# pwm-dac-rev2.net
KiCad netlist of a schematic drawn in EAGLE
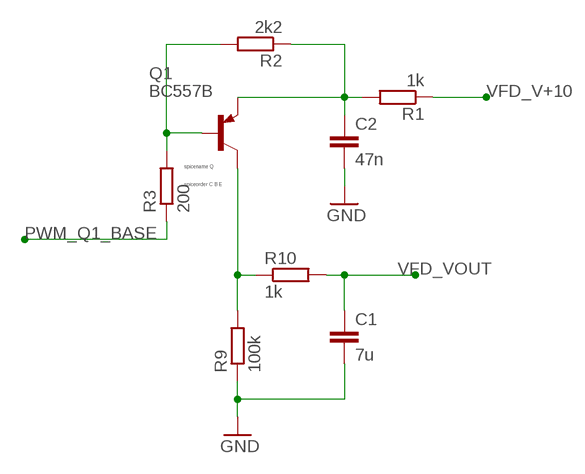
[diagram p0: schematic, sheet 1]
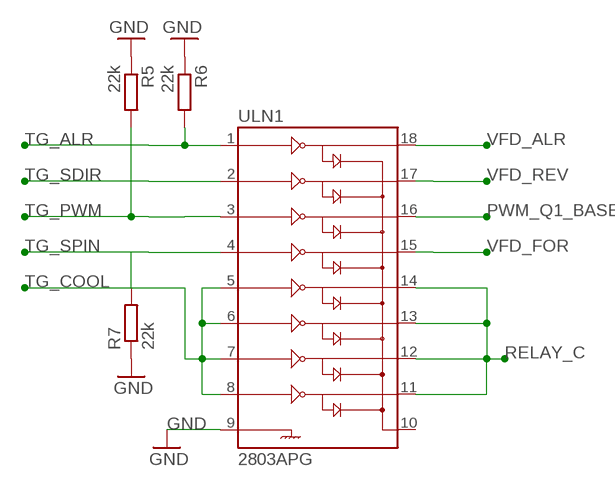
[diagram p1: schematic, sheet 2]
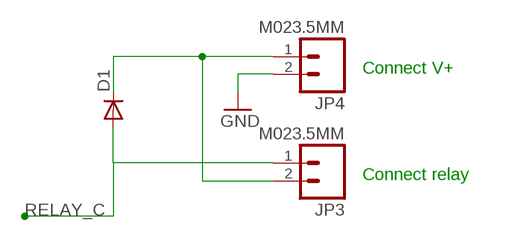
[diagram p2: schematic, sheet 3]
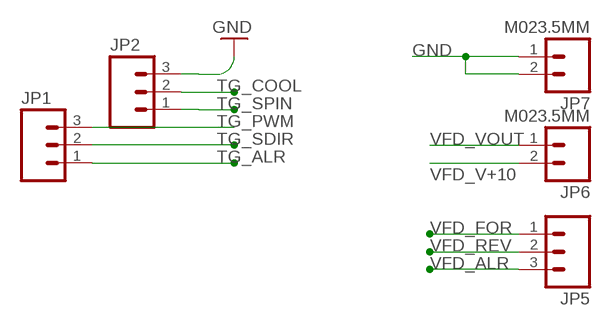
[diagram p3: schematic, sheet 4]

(export (version "E")
  (design (tool "Eeschema 10.0.6"))
  (components
    (comp (ref "C1")
      (value "7u")
      (footprint "eagle-import:C025-025X050")
      (libsource (lib "eagle-import") (part "C-EU025-025X050"))
    )
    (comp (ref "C2")
      (value "47n")
      (footprint "eagle-import:C025-025X050")
      (libsource (lib "eagle-import") (part "C-EU025-025X050"))
    )
    (comp (ref "Q1")
      (value "BC557B")
      (footprint "eagle-import:TO92-EBC-OVAL")
      (libsource (lib "eagle-import") (part "2N2907"))
    )
    (comp (ref "R1")
      (value "1k")
      (footprint "eagle-import:0204_7")
      (libsource (lib "eagle-import") (part "R-EU_0204/7"))
    )
    (comp (ref "R2")
      (value "2k2")
      (footprint "eagle-import:0204_7")
      (libsource (lib "eagle-import") (part "R-EU_0204/7"))
    )
    (comp (ref "R3")
      (value "200")
      (footprint "eagle-import:0204_7")
      (libsource (lib "eagle-import") (part "R-EU_0204/7"))
    )
    (comp (ref "R9")
      (value "100k")
      (footprint "eagle-import:0204_7")
      (libsource (lib "eagle-import") (part "R-EU_0204/7"))
    )
    (comp (ref "R10")
      (value "1k")
      (footprint "eagle-import:0204_7")
      (libsource (lib "eagle-import") (part "R-EU_0204/7"))
    )
    (comp (ref "JP1")
      (value "M03SCREW")
      (footprint "eagle-import:SCREWTERMINAL-3.5MM-3")
      (libsource (lib "eagle-import") (part "M03SCREW"))
    )
    (comp (ref "JP2")
      (value "M03SCREW")
      (footprint "eagle-import:SCREWTERMINAL-3.5MM-3")
      (libsource (lib "eagle-import") (part "M03SCREW"))
    )
    (comp (ref "JP5")
      (value "M03SCREW")
      (footprint "eagle-import:SCREWTERMINAL-3.5MM-3")
      (libsource (lib "eagle-import") (part "M03SCREW"))
    )
    (comp (ref "JP6")
      (value "M023.5MM")
      (footprint "eagle-import:SCREWTERMINAL-3.5MM-2")
      (libsource (lib "eagle-import") (part "M023.5MM"))
    )
    (comp (ref "JP7")
      (value "M023.5MM")
      (footprint "eagle-import:SCREWTERMINAL-3.5MM-2")
      (libsource (lib "eagle-import") (part "M023.5MM"))
    )
    (comp (ref "R5")
      (value "22k")
      (footprint "eagle-import:0204_7")
      (libsource (lib "eagle-import") (part "R-EU_0204/7"))
    )
    (comp (ref "R6")
      (value "22k")
      (footprint "eagle-import:0204_7")
      (libsource (lib "eagle-import") (part "R-EU_0204/7"))
    )
    (comp (ref "R7")
      (value "22k")
      (footprint "eagle-import:0204_7")
      (libsource (lib "eagle-import") (part "R-EU_0204/7"))
    )
    (comp (ref "ULN1")
      (value "2803APG")
      (footprint "eagle-import:DIL18")
      (libsource (lib "eagle-import") (part "ULN2803DIP"))
    )
    (comp (ref "D1")
      (value "DIODE1N4148")
      (footprint "eagle-import:DIODE-1N4148")
      (libsource (lib "eagle-import") (part "DIODE1N4148"))
    )
    (comp (ref "JP3")
      (value "M023.5MM")
      (footprint "eagle-import:SCREWTERMINAL-3.5MM-2")
      (libsource (lib "eagle-import") (part "M023.5MM"))
    )
    (comp (ref "JP4")
      (value "M023.5MM")
      (footprint "eagle-import:SCREWTERMINAL-3.5MM-2")
      (libsource (lib "eagle-import") (part "M023.5MM"))
    )
  )
  (nets
    (net (code "1") (name "GND") (class "Default")
      (node (ref "C1") (pin "2") (pinfunction "2_2") (pintype "passive"))
      (node (ref "C2") (pin "2") (pinfunction "2_2") (pintype "passive"))
      (node (ref "JP2") (pin "3") (pinfunction "3_3") (pintype "passive"))
      (node (ref "JP4") (pin "2") (pinfunction "2_2") (pintype "passive"))
      (node (ref "JP7") (pin "1") (pinfunction "1_1") (pintype "passive"))
      (node (ref "JP7") (pin "2") (pinfunction "2_2") (pintype "passive"))
      (node (ref "R5") (pin "1") (pinfunction "1_1") (pintype "passive"))
      (node (ref "R6") (pin "1") (pinfunction "1_1") (pintype "passive"))
      (node (ref "R7") (pin "1") (pinfunction "1_1") (pintype "passive"))
      (node (ref "R9") (pin "1") (pinfunction "1_1") (pintype "passive"))
      (node (ref "ULN1") (pin "9") (pinfunction "9_9") (pintype "bidirectional"))
    )
    (net (code "2") (name "Net-(C2-Pad1)") (class "Default")
      (node (ref "C2") (pin "1") (pinfunction "1_1") (pintype "passive"))
      (node (ref "Q1") (pin "E") (pinfunction "E_E") (pintype "passive"))
      (node (ref "R1") (pin "2") (pinfunction "2_2") (pintype "passive"))
      (node (ref "R2") (pin "1") (pinfunction "1_1") (pintype "passive"))
    )
    (net (code "3") (name "Net-(D1-PadC)") (class "Default")
      (node (ref "D1") (pin "C") (pinfunction "C_C") (pintype "passive"))
      (node (ref "JP3") (pin "2") (pinfunction "2_2") (pintype "passive"))
      (node (ref "JP4") (pin "1") (pinfunction "1_1") (pintype "passive"))
    )
    (net (code "4") (name "Net-(Q1-PadB)") (class "Default")
      (node (ref "Q1") (pin "B") (pinfunction "B_B") (pintype "passive"))
      (node (ref "R2") (pin "2") (pinfunction "2_2") (pintype "passive"))
      (node (ref "R3") (pin "2") (pinfunction "2_2") (pintype "passive"))
    )
    (net (code "5") (name "Net-(Q1-PadC)") (class "Default")
      (node (ref "Q1") (pin "C") (pinfunction "C_C") (pintype "passive"))
      (node (ref "R10") (pin "1") (pinfunction "1_1") (pintype "passive"))
      (node (ref "R9") (pin "2") (pinfunction "2_2") (pintype "passive"))
    )
    (net (code "6") (name "PWM_Q1_BASE") (class "Default")
      (node (ref "R3") (pin "1") (pinfunction "1_1") (pintype "passive"))
      (node (ref "ULN1") (pin "16") (pinfunction "16_16") (pintype "bidirectional"))
    )
    (net (code "7") (name "RELAY_C") (class "Default")
      (node (ref "D1") (pin "A") (pinfunction "A_A") (pintype "passive"))
      (node (ref "JP3") (pin "1") (pinfunction "1_1") (pintype "passive"))
      (node (ref "ULN1") (pin "11") (pinfunction "11_11") (pintype "bidirectional"))
      (node (ref "ULN1") (pin "12") (pinfunction "12_12") (pintype "bidirectional"))
      (node (ref "ULN1") (pin "13") (pinfunction "13_13") (pintype "bidirectional"))
      (node (ref "ULN1") (pin "14") (pinfunction "14_14") (pintype "bidirectional"))
    )
    (net (code "8") (name "TG_ALR") (class "Default")
      (node (ref "JP1") (pin "1") (pinfunction "1_1") (pintype "passive"))
      (node (ref "R6") (pin "2") (pinfunction "2_2") (pintype "passive"))
      (node (ref "ULN1") (pin "1") (pinfunction "1_1") (pintype "bidirectional"))
    )
    (net (code "9") (name "TG_COOL") (class "Default")
      (node (ref "JP2") (pin "2") (pinfunction "2_2") (pintype "passive"))
      (node (ref "ULN1") (pin "5") (pinfunction "5_5") (pintype "bidirectional"))
      (node (ref "ULN1") (pin "6") (pinfunction "6_6") (pintype "bidirectional"))
      (node (ref "ULN1") (pin "7") (pinfunction "7_7") (pintype "bidirectional"))
      (node (ref "ULN1") (pin "8") (pinfunction "8_8") (pintype "bidirectional"))
    )
    (net (code "10") (name "TG_PWM") (class "Default")
      (node (ref "JP1") (pin "3") (pinfunction "3_3") (pintype "passive"))
      (node (ref "R5") (pin "2") (pinfunction "2_2") (pintype "passive"))
      (node (ref "ULN1") (pin "3") (pinfunction "3_3") (pintype "bidirectional"))
    )
    (net (code "11") (name "TG_SDIR") (class "Default")
      (node (ref "JP1") (pin "2") (pinfunction "2_2") (pintype "passive"))
      (node (ref "ULN1") (pin "2") (pinfunction "2_2") (pintype "bidirectional"))
    )
    (net (code "12") (name "TG_SPIN") (class "Default")
      (node (ref "JP2") (pin "1") (pinfunction "1_1") (pintype "passive"))
      (node (ref "R7") (pin "2") (pinfunction "2_2") (pintype "passive"))
      (node (ref "ULN1") (pin "4") (pinfunction "4_4") (pintype "bidirectional"))
    )
    (net (code "13") (name "VFD_ALR") (class "Default")
      (node (ref "JP5") (pin "3") (pinfunction "3_3") (pintype "passive"))
      (node (ref "ULN1") (pin "18") (pinfunction "18_18") (pintype "bidirectional"))
    )
    (net (code "14") (name "VFD_FOR") (class "Default")
      (node (ref "JP5") (pin "1") (pinfunction "1_1") (pintype "passive"))
      (node (ref "ULN1") (pin "15") (pinfunction "15_15") (pintype "bidirectional"))
    )
    (net (code "15") (name "VFD_REV") (class "Default")
      (node (ref "JP5") (pin "2") (pinfunction "2_2") (pintype "passive"))
      (node (ref "ULN1") (pin "17") (pinfunction "17_17") (pintype "bidirectional"))
    )
    (net (code "16") (name "VFD_V+10") (class "Default")
      (node (ref "JP6") (pin "2") (pinfunction "2_2") (pintype "passive"))
      (node (ref "R1") (pin "1") (pinfunction "1_1") (pintype "passive"))
    )
    (net (code "17") (name "VFD_VOUT") (class "Default")
      (node (ref "C1") (pin "1") (pinfunction "1_1") (pintype "passive"))
      (node (ref "JP6") (pin "1") (pinfunction "1_1") (pintype "passive"))
      (node (ref "R10") (pin "2") (pinfunction "2_2") (pintype "passive"))
    )
    (net (code "18") (name "unconnected-(ULN1-Pad10)") (class "Default")
      (node (ref "ULN1") (pin "10") (pinfunction "10_10") (pintype "bidirectional"))
    )
  )
)
